# DRLPWM.net
KiCad netlist of a schematic drawn in Altium Designer
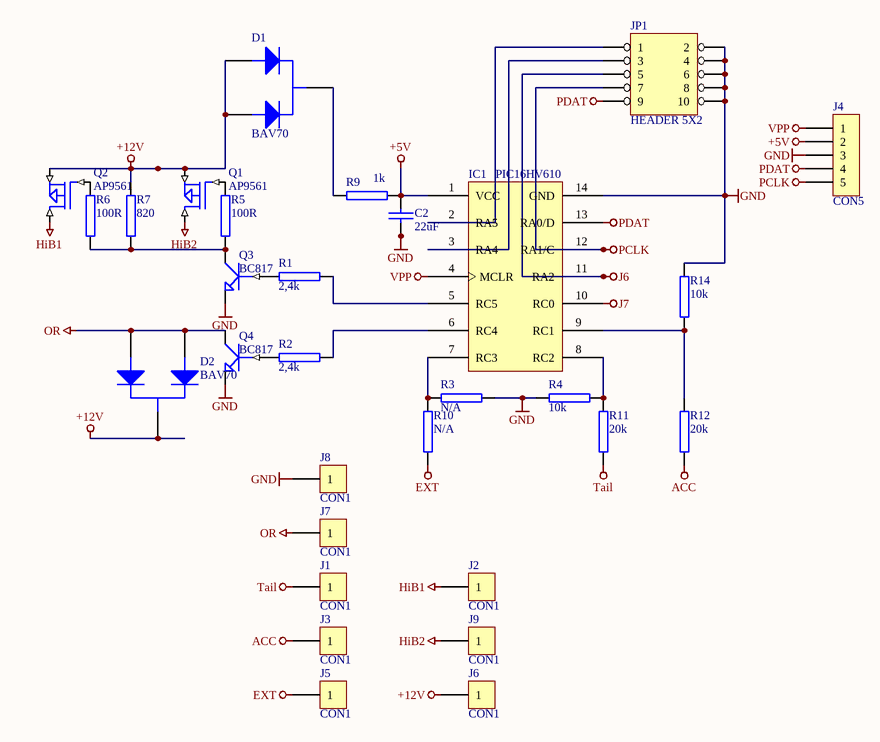
[diagram p0: DRLPWM.SchDoc]

(export (version "E")
  (design (tool "Eeschema 10.0.6"))
  (components
    (comp (ref "C2") (value "22uF") (footprint "0805") (libsource (lib "*") (part "CAP")))
    (comp (ref "D1")
      (value "BAV70")
      (footprint "SOT-23")
      (libsource (lib "Devices") (part "DUAL DIODE BAV70"))
    )
    (comp (ref "D2")
      (value "BAV70")
      (footprint "SOT-23")
      (libsource (lib "Devices") (part "DUAL DIODE BAV70"))
    )
    (comp (ref "IC1") (value "PIC16HV610") (footprint "SO-14") (libsource (lib "*") (part "PIC16HV610")))
    (comp (ref "J1")
      (value "CON1")
      (footprint "SIP1 - WIRE")
      (description "Connector")
      (libsource (lib "Miscellaneous Devices") (part "CON1"))
    )
    (comp (ref "J2")
      (value "CON1")
      (footprint "SIP1 - WIRE")
      (description "Connector")
      (libsource (lib "Miscellaneous Devices") (part "CON1"))
    )
    (comp (ref "J3")
      (value "CON1")
      (footprint "SIP1 - WIRE")
      (description "Connector")
      (libsource (lib "Miscellaneous Devices") (part "CON1"))
    )
    (comp (ref "J4")
      (value "CON5")
      (footprint "SIP5 - PGM")
      (description "Connector")
      (libsource (lib "Miscellaneous Devices") (part "CON5"))
    )
    (comp (ref "J5")
      (value "CON1")
      (footprint "SIP1 - WIRE")
      (description "Connector")
      (libsource (lib "Miscellaneous Devices") (part "CON1"))
    )
    (comp (ref "J6")
      (value "CON1")
      (footprint "SIP1 - WIRE")
      (description "Connector")
      (libsource (lib "Miscellaneous Devices") (part "CON1"))
    )
    (comp (ref "J7")
      (value "CON1")
      (footprint "SIP1 - WIRE")
      (description "Connector")
      (libsource (lib "Miscellaneous Devices") (part "CON1"))
    )
    (comp (ref "J8")
      (value "CON1")
      (footprint "SIP1 - WIRE")
      (description "Connector")
      (libsource (lib "Miscellaneous Devices") (part "CON1"))
    )
    (comp (ref "J9")
      (value "CON1")
      (footprint "SIP1 - WIRE")
      (description "Connector")
      (libsource (lib "Miscellaneous Devices") (part "CON1"))
    )
    (comp (ref "JP1")
      (value "HEADER 5X2")
      (footprint "IDC10")
      (libsource (lib "Miscellaneous Devices") (part "HEADER 5X2"))
    )
    (comp (ref "Q1") (value "AP9561") (footprint "D-Pack") (libsource (lib "*") (part "MOSFET P")))
    (comp (ref "Q2") (value "AP9561") (footprint "D-Pack") (libsource (lib "*") (part "MOSFET P")))
    (comp (ref "Q3")
      (value "BC817")
      (footprint "SOT-23")
      (description "NPN Transistor")
      (libsource (lib "Miscellaneous Devices") (part "NPN1"))
    )
    (comp (ref "Q4")
      (value "BC817")
      (footprint "SOT-23")
      (description "NPN Transistor")
      (libsource (lib "Miscellaneous Devices") (part "NPN1"))
    )
    (comp (ref "R1") (value "2,4k") (footprint "0805") (libsource (lib "*") (part "RES2")))
    (comp (ref "R2") (value "2,4k") (footprint "0805") (libsource (lib "*") (part "RES2")))
    (comp (ref "R3") (value "N/A") (footprint "0805") (libsource (lib "*") (part "RES2")))
    (comp (ref "R4") (value "10k") (footprint "0805") (libsource (lib "*") (part "RES2")))
    (comp (ref "R5") (value "100R") (footprint "0805") (libsource (lib "*") (part "RES2")))
    (comp (ref "R6") (value "100R") (footprint "0805") (libsource (lib "*") (part "RES2")))
    (comp (ref "R7") (value "820") (footprint "0805") (libsource (lib "*") (part "RES2")))
    (comp (ref "R9") (value "1k") (footprint "0805") (libsource (lib "*") (part "RES2")))
    (comp (ref "R10") (value "N/A") (footprint "0805") (libsource (lib "*") (part "RES2")))
    (comp (ref "R11") (value "20k") (footprint "0805") (libsource (lib "*") (part "RES2")))
    (comp (ref "R12") (value "20k") (footprint "0805") (libsource (lib "*") (part "RES2")))
    (comp (ref "R14") (value "10k") (footprint "0805") (libsource (lib "*") (part "RES2")))
  )
  (nets
    (net (code "1") (name "+5V") (class "Default")
      (node (ref "C2") (pin "1") (pintype "passive"))
      (node (ref "IC1") (pin "1") (pinfunction "VCC_1") (pintype "power_in"))
      (node (ref "J4") (pin "2") (pinfunction "2_2") (pintype "passive"))
      (node (ref "R9") (pin "2") (pintype "passive"))
    )
    (net (code "2") (name "+12V") (class "Default")
      (node (ref "D1") (pin "1") (pinfunction "A1_1") (pintype "passive"))
      (node (ref "D1") (pin "3") (pinfunction "A2_3") (pintype "passive"))
      (node (ref "D2") (pin "2") (pinfunction "K_2") (pintype "passive"))
      (node (ref "J6") (pin "1") (pinfunction "1_1") (pintype "passive"))
      (node (ref "Q1") (pin "3") (pinfunction "SOURCE_3") (pintype "input"))
      (node (ref "Q2") (pin "3") (pinfunction "SOURCE_3") (pintype "input"))
      (node (ref "R7") (pin "2") (pintype "passive"))
    )
    (net (code "3") (name "ACC") (class "Default")
      (node (ref "J3") (pin "1") (pinfunction "1_1") (pintype "passive"))
      (node (ref "R12") (pin "1") (pintype "passive"))
    )
    (net (code "4") (name "EXT") (class "Default")
      (node (ref "J5") (pin "1") (pinfunction "1_1") (pintype "passive"))
      (node (ref "R10") (pin "1") (pintype "passive"))
    )
    (net (code "5") (name "GND") (class "Default")
      (node (ref "C2") (pin "2") (pintype "passive"))
      (node (ref "IC1") (pin "14") (pinfunction "GND_14") (pintype "power_in"))
      (node (ref "J4") (pin "3") (pinfunction "3_3") (pintype "passive"))
      (node (ref "J8") (pin "1") (pinfunction "1_1") (pintype "passive"))
      (node (ref "JP1") (pin "10") (pinfunction "10_10") (pintype "passive"))
      (node (ref "JP1") (pin "2") (pinfunction "2_2") (pintype "passive"))
      (node (ref "JP1") (pin "4") (pinfunction "4_4") (pintype "passive"))
      (node (ref "JP1") (pin "6") (pinfunction "6_6") (pintype "passive"))
      (node (ref "JP1") (pin "8") (pinfunction "8_8") (pintype "passive"))
      (node (ref "Q3") (pin "3") (pinfunction "E_3") (pintype "passive"))
      (node (ref "Q4") (pin "3") (pinfunction "E_3") (pintype "passive"))
      (node (ref "R14") (pin "2") (pintype "passive"))
      (node (ref "R3") (pin "2") (pintype "passive"))
      (node (ref "R4") (pin "1") (pintype "passive"))
    )
    (net (code "6") (name "HiB1") (class "Default")
      (node (ref "J2") (pin "1") (pinfunction "1_1") (pintype "passive"))
      (node (ref "Q2") (pin "2") (pinfunction "DRAIN_2") (pintype "input"))
    )
    (net (code "7") (name "HiB2") (class "Default")
      (node (ref "J9") (pin "1") (pinfunction "1_1") (pintype "passive"))
      (node (ref "Q1") (pin "2") (pinfunction "DRAIN_2") (pintype "input"))
    )
    (net (code "8") (name "J6") (class "Default")
      (node (ref "IC1") (pin "11") (pinfunction "RA2_11") (pintype "passive"))
      (node (ref "JP1") (pin "5") (pinfunction "5_5") (pintype "passive"))
    )
    (net (code "9") (name "J7") (class "Default")
      (node (ref "IC1") (pin "10") (pinfunction "RC0_10") (pintype "passive"))
    )
    (net (code "10") (name "Net-(D1-K)") (class "Default")
      (node (ref "D1") (pin "2") (pinfunction "K_2") (pintype "passive"))
      (node (ref "R9") (pin "1") (pintype "passive"))
    )
    (net (code "11") (name "Net-(IC1-RA4)") (class "Default")
      (node (ref "IC1") (pin "3") (pinfunction "RA4_3") (pintype "passive"))
      (node (ref "JP1") (pin "3") (pinfunction "3_3") (pintype "passive"))
    )
    (net (code "12") (name "Net-(IC1-RA5)") (class "Default")
      (node (ref "IC1") (pin "2") (pinfunction "RA5_2") (pintype "passive"))
      (node (ref "JP1") (pin "1") (pinfunction "1_1") (pintype "passive"))
    )
    (net (code "13") (name "Net-(IC1-RC1)") (class "Default")
      (node (ref "IC1") (pin "9") (pinfunction "RC1_9") (pintype "passive"))
      (node (ref "R12") (pin "2") (pintype "passive"))
      (node (ref "R14") (pin "1") (pintype "passive"))
    )
    (net (code "14") (name "Net-(IC1-RC2)") (class "Default")
      (node (ref "IC1") (pin "8") (pinfunction "RC2_8") (pintype "passive"))
      (node (ref "R11") (pin "2") (pintype "passive"))
      (node (ref "R4") (pin "2") (pintype "passive"))
    )
    (net (code "15") (name "Net-(IC1-RC3)") (class "Default")
      (node (ref "IC1") (pin "7") (pinfunction "RC3_7") (pintype "passive"))
      (node (ref "R10") (pin "2") (pintype "passive"))
      (node (ref "R3") (pin "1") (pintype "passive"))
    )
    (net (code "16") (name "Net-(IC1-RC4)") (class "Default")
      (node (ref "IC1") (pin "6") (pinfunction "RC4_6") (pintype "passive"))
      (node (ref "R2") (pin "2") (pintype "passive"))
    )
    (net (code "17") (name "Net-(IC1-RC5)") (class "Default")
      (node (ref "IC1") (pin "5") (pinfunction "RC5_5") (pintype "passive"))
      (node (ref "R1") (pin "2") (pintype "passive"))
    )
    (net (code "18") (name "Net-(Q1-GATE)") (class "Default")
      (node (ref "Q1") (pin "1") (pinfunction "GATE_1") (pintype "input"))
      (node (ref "R5") (pin "2") (pintype "passive"))
    )
    (net (code "19") (name "Net-(Q2-GATE)") (class "Default")
      (node (ref "Q2") (pin "1") (pinfunction "GATE_1") (pintype "input"))
      (node (ref "R6") (pin "2") (pintype "passive"))
    )
    (net (code "20") (name "Net-(Q3-B)") (class "Default")
      (node (ref "Q3") (pin "1") (pinfunction "B_1") (pintype "input"))
      (node (ref "R1") (pin "1") (pintype "passive"))
    )
    (net (code "21") (name "Net-(Q3-C)") (class "Default")
      (node (ref "Q3") (pin "2") (pinfunction "C_2") (pintype "passive"))
      (node (ref "R5") (pin "1") (pintype "passive"))
      (node (ref "R6") (pin "1") (pintype "passive"))
      (node (ref "R7") (pin "1") (pintype "passive"))
    )
    (net (code "22") (name "Net-(Q4-B)") (class "Default")
      (node (ref "Q4") (pin "1") (pinfunction "B_1") (pintype "input"))
      (node (ref "R2") (pin "1") (pintype "passive"))
    )
    (net (code "23") (name "OR") (class "Default")
      (node (ref "D2") (pin "1") (pinfunction "A1_1") (pintype "passive"))
      (node (ref "D2") (pin "3") (pinfunction "A2_3") (pintype "passive"))
      (node (ref "J7") (pin "1") (pinfunction "1_1") (pintype "passive"))
      (node (ref "Q4") (pin "2") (pinfunction "C_2") (pintype "passive"))
    )
    (net (code "24") (name "PCLK") (class "Default")
      (node (ref "IC1") (pin "12") (pinfunction "RA1/C_12") (pintype "passive"))
      (node (ref "J4") (pin "5") (pinfunction "5_5") (pintype "passive"))
      (node (ref "JP1") (pin "7") (pinfunction "7_7") (pintype "passive"))
    )
    (net (code "25") (name "PDAT") (class "Default")
      (node (ref "IC1") (pin "13") (pinfunction "RA0/D_13") (pintype "passive"))
      (node (ref "J4") (pin "4") (pinfunction "4_4") (pintype "passive"))
      (node (ref "JP1") (pin "9") (pinfunction "9_9") (pintype "passive"))
    )
    (net (code "26") (name "Tail") (class "Default")
      (node (ref "J1") (pin "1") (pinfunction "1_1") (pintype "passive"))
      (node (ref "R11") (pin "1") (pintype "passive"))
    )
    (net (code "27") (name "VPP") (class "Default")
      (node (ref "IC1") (pin "4") (pinfunction "MCLR_4") (pintype "passive"))
      (node (ref "J4") (pin "1") (pinfunction "1_1") (pintype "passive"))
    )
  )
)
